# doorbellboard.net
KiCad netlist of a schematic drawn in EAGLE
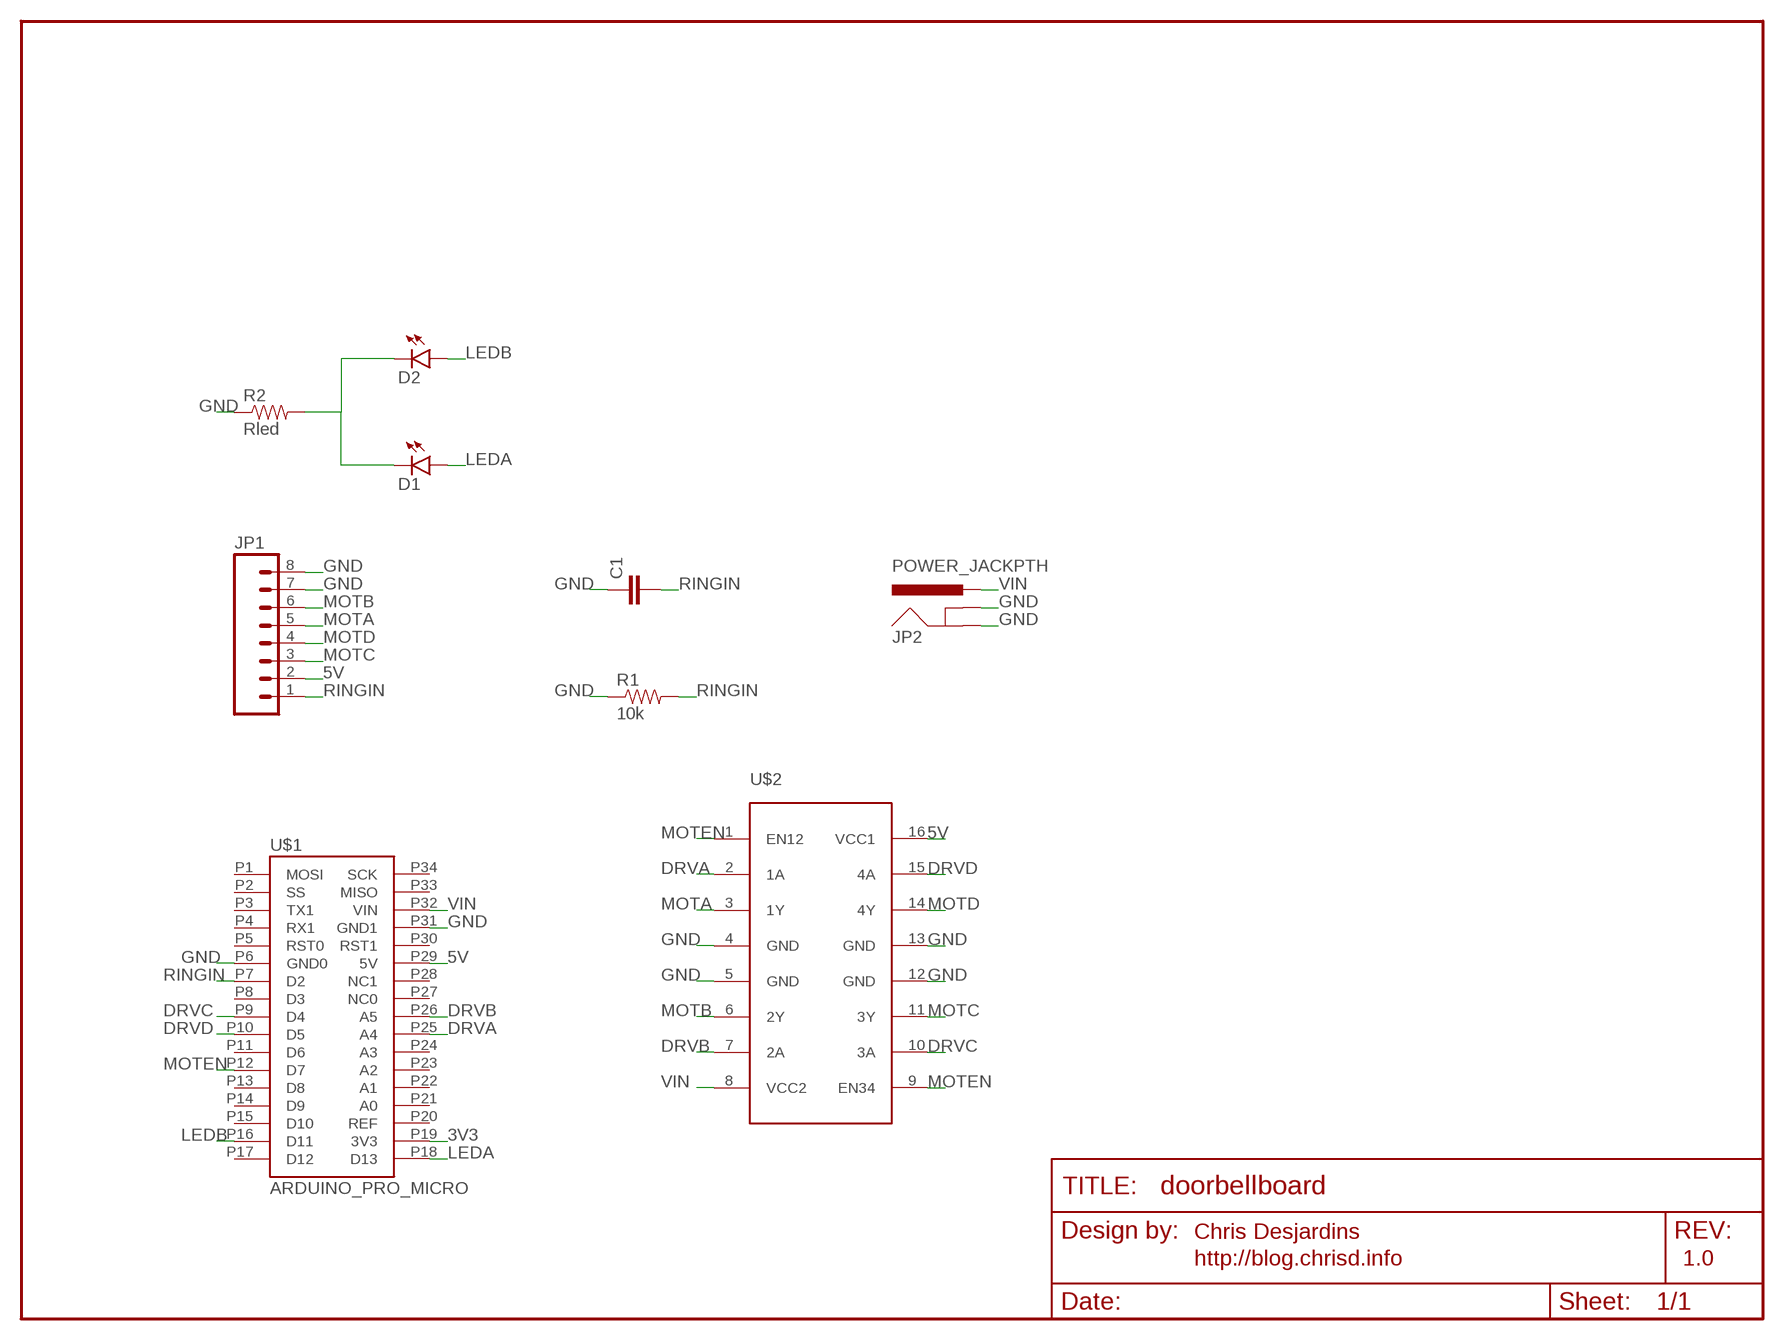
[diagram p0: schematic, sheet 1]

(export (version "E")
  (design (tool "Eeschema 10.0.6"))
  (components
    (comp (ref "C1")
      (value "0.1UF-50V-20%(PTH)KIT-EZ")
      (footprint "eagle-import:CAP-PTH-SMALL-KIT")
      (libsource (lib "eagle-import") (part "0.1UF-50V-20%(PTH)KIT-EZ"))
    )
    (comp (ref "D1")
      (value "LED-3MM-NO_SILK")
      (footprint "eagle-import:LED3MM-NS")
      (libsource (lib "eagle-import") (part "LED-3MM-NO_SILK"))
    )
    (comp (ref "D2")
      (value "LED-3MM-NO_SILK")
      (footprint "eagle-import:LED3MM-NS")
      (libsource (lib "eagle-import") (part "LED-3MM-NO_SILK"))
    )
    (comp (ref "JP1")
      (value "M08")
      (footprint "eagle-import:1X08_ROUND")
      (libsource (lib "eagle-import") (part "M08"))
    )
    (comp (ref "JP2")
      (value "POWER_JACKPTH")
      (footprint "eagle-import:POWER_JACK_PTH")
      (libsource (lib "eagle-import") (part "POWER_JACKPTH"))
    )
    (comp (ref "R1")
      (value "10k")
      (footprint "eagle-import:AXIAL-0.3")
      (libsource (lib "eagle-import") (part "10KOHM-1/4W-1%(PTH)HORIZ"))
    )
    (comp (ref "R2")
      (value "Rled")
      (footprint "eagle-import:AXIAL-0.3")
      (libsource (lib "eagle-import") (part "10KOHM-1/4W-1%(PTH)HORIZ"))
    )
    (comp (ref "U$1")
      (value "ARDUINO_PRO_MICRO")
      (footprint "eagle-import:ARDUINO_PRO_MICRO")
      (libsource (lib "eagle-import") (part "ARDUINO_PRO_MICRO"))
    )
    (comp (ref "U$2")
      (value "SN754410")
      (footprint "eagle-import:DIL16-KIT")
      (libsource (lib "eagle-import") (part "SN754410"))
    )
  )
  (nets
    (net (code "1") (name "/3V3") (class "Default")
      (node (ref "U$1") (pin "P19") (pinfunction "3V3_P19") (pintype "power_in"))
    )
    (net (code "2") (name "/5V") (class "Default")
      (node (ref "JP1") (pin "2") (pinfunction "2_2") (pintype "passive"))
      (node (ref "U$1") (pin "P29") (pinfunction "5V_P29") (pintype "power_in"))
      (node (ref "U$2") (pin "16") (pinfunction "VCC1_16") (pintype "bidirectional"))
    )
    (net (code "3") (name "/DRVA") (class "Default")
      (node (ref "U$1") (pin "P25") (pinfunction "A4_P25") (pintype "bidirectional"))
      (node (ref "U$2") (pin "2") (pinfunction "1A_2") (pintype "bidirectional"))
    )
    (net (code "4") (name "/DRVB") (class "Default")
      (node (ref "U$1") (pin "P26") (pinfunction "A5_P26") (pintype "bidirectional"))
      (node (ref "U$2") (pin "7") (pinfunction "2A_7") (pintype "bidirectional"))
    )
    (net (code "5") (name "/DRVC") (class "Default")
      (node (ref "U$1") (pin "P9") (pinfunction "D4_P9") (pintype "bidirectional"))
      (node (ref "U$2") (pin "10") (pinfunction "3A_10") (pintype "bidirectional"))
    )
    (net (code "6") (name "/DRVD") (class "Default")
      (node (ref "U$1") (pin "P10") (pinfunction "D5_P10") (pintype "bidirectional"))
      (node (ref "U$2") (pin "15") (pinfunction "4A_15") (pintype "bidirectional"))
    )
    (net (code "7") (name "/GND") (class "Default")
      (node (ref "C1") (pin "1") (pinfunction "1_1") (pintype "passive"))
      (node (ref "JP1") (pin "7") (pinfunction "7_7") (pintype "passive"))
      (node (ref "JP1") (pin "8") (pinfunction "8_8") (pintype "passive"))
      (node (ref "JP2") (pin "GND") (pinfunction "GND_GND") (pintype "bidirectional"))
      (node (ref "JP2") (pin "GNDBREAK") (pinfunction "GNDBREAK_GNDBREAK") (pintype "bidirectional"))
      (node (ref "R1") (pin "P$1") (pinfunction "1_P$1") (pintype "passive"))
      (node (ref "R2") (pin "P$1") (pinfunction "1_P$1") (pintype "passive"))
      (node (ref "U$1") (pin "P31") (pinfunction "GND1_P31") (pintype "power_in"))
      (node (ref "U$1") (pin "P6") (pinfunction "GND0_P6") (pintype "power_in"))
      (node (ref "U$2") (pin "12") (pinfunction "GND_12") (pintype "bidirectional"))
      (node (ref "U$2") (pin "13") (pinfunction "GND_13") (pintype "bidirectional"))
      (node (ref "U$2") (pin "4") (pinfunction "GND_4") (pintype "bidirectional"))
      (node (ref "U$2") (pin "5") (pinfunction "GND_5") (pintype "bidirectional"))
    )
    (net (code "8") (name "/LEDA") (class "Default")
      (node (ref "D1") (pin "A") (pinfunction "A_A") (pintype "passive"))
      (node (ref "U$1") (pin "P18") (pinfunction "D13_P18") (pintype "bidirectional"))
    )
    (net (code "9") (name "/LEDB") (class "Default")
      (node (ref "D2") (pin "A") (pinfunction "A_A") (pintype "passive"))
      (node (ref "U$1") (pin "P16") (pinfunction "D11_P16") (pintype "bidirectional"))
    )
    (net (code "10") (name "/MOTA") (class "Default")
      (node (ref "JP1") (pin "5") (pinfunction "5_5") (pintype "passive"))
      (node (ref "U$2") (pin "3") (pinfunction "1Y_3") (pintype "bidirectional"))
    )
    (net (code "11") (name "/MOTB") (class "Default")
      (node (ref "JP1") (pin "6") (pinfunction "6_6") (pintype "passive"))
      (node (ref "U$2") (pin "6") (pinfunction "2Y_6") (pintype "bidirectional"))
    )
    (net (code "12") (name "/MOTC") (class "Default")
      (node (ref "JP1") (pin "3") (pinfunction "3_3") (pintype "passive"))
      (node (ref "U$2") (pin "11") (pinfunction "3Y_11") (pintype "bidirectional"))
    )
    (net (code "13") (name "/MOTD") (class "Default")
      (node (ref "JP1") (pin "4") (pinfunction "4_4") (pintype "passive"))
      (node (ref "U$2") (pin "14") (pinfunction "4Y_14") (pintype "bidirectional"))
    )
    (net (code "14") (name "/MOTEN") (class "Default")
      (node (ref "U$1") (pin "P12") (pinfunction "D7_P12") (pintype "bidirectional"))
      (node (ref "U$2") (pin "1") (pinfunction "EN12_1") (pintype "bidirectional"))
      (node (ref "U$2") (pin "9") (pinfunction "EN34_9") (pintype "bidirectional"))
    )
    (net (code "15") (name "/REF") (class "Default")
      (node (ref "U$1") (pin "P20") (pinfunction "REF_P20") (pintype "power_in"))
    )
    (net (code "16") (name "/RINGIN") (class "Default")
      (node (ref "C1") (pin "2") (pinfunction "2_2") (pintype "passive"))
      (node (ref "JP1") (pin "1") (pinfunction "1_1") (pintype "passive"))
      (node (ref "R1") (pin "P$2") (pinfunction "2_P$2") (pintype "passive"))
      (node (ref "U$1") (pin "P7") (pinfunction "D2_P7") (pintype "bidirectional"))
    )
    (net (code "17") (name "/VIN") (class "Default")
      (node (ref "JP2") (pin "PWR") (pinfunction "PWR_PWR") (pintype "bidirectional"))
      (node (ref "U$1") (pin "P32") (pinfunction "VIN_P32") (pintype "power_in"))
      (node (ref "U$2") (pin "8") (pinfunction "VCC2_8") (pintype "bidirectional"))
    )
    (net (code "18") (name "Net-(D1-C)") (class "Default")
      (node (ref "D1") (pin "K") (pinfunction "C_K") (pintype "passive"))
      (node (ref "D2") (pin "K") (pinfunction "C_K") (pintype "passive"))
      (node (ref "R2") (pin "P$2") (pinfunction "2_P$2") (pintype "passive"))
    )
    (net (code "19") (name "unconnected-(U$1-A0-PadP21)") (class "Default")
      (node (ref "U$1") (pin "P21") (pinfunction "A0_P21") (pintype "bidirectional"))
    )
    (net (code "20") (name "unconnected-(U$1-A1-PadP22)") (class "Default")
      (node (ref "U$1") (pin "P22") (pinfunction "A1_P22") (pintype "bidirectional"))
    )
    (net (code "21") (name "unconnected-(U$1-A2-PadP23)") (class "Default")
      (node (ref "U$1") (pin "P23") (pinfunction "A2_P23") (pintype "bidirectional"))
    )
    (net (code "22") (name "unconnected-(U$1-A3-PadP24)") (class "Default")
      (node (ref "U$1") (pin "P24") (pinfunction "A3_P24") (pintype "bidirectional"))
    )
    (net (code "23") (name "unconnected-(U$1-D3-PadP8)") (class "Default")
      (node (ref "U$1") (pin "P8") (pinfunction "D3_P8") (pintype "bidirectional"))
    )
    (net (code "24") (name "unconnected-(U$1-D6-PadP11)") (class "Default")
      (node (ref "U$1") (pin "P11") (pinfunction "D6_P11") (pintype "bidirectional"))
    )
    (net (code "25") (name "unconnected-(U$1-D8-PadP13)") (class "Default")
      (node (ref "U$1") (pin "P13") (pinfunction "D8_P13") (pintype "bidirectional"))
    )
    (net (code "26") (name "unconnected-(U$1-D9-PadP14)") (class "Default")
      (node (ref "U$1") (pin "P14") (pinfunction "D9_P14") (pintype "bidirectional"))
    )
    (net (code "27") (name "unconnected-(U$1-D10-PadP15)") (class "Default")
      (node (ref "U$1") (pin "P15") (pinfunction "D10_P15") (pintype "bidirectional"))
    )
    (net (code "28") (name "unconnected-(U$1-D12-PadP17)") (class "Default")
      (node (ref "U$1") (pin "P17") (pinfunction "D12_P17") (pintype "bidirectional"))
    )
    (net (code "29") (name "unconnected-(U$1-MISO-PadP33)") (class "Default")
      (node (ref "U$1") (pin "P33") (pinfunction "MISO_P33") (pintype "bidirectional"))
    )
    (net (code "30") (name "unconnected-(U$1-MOSI-PadP1)") (class "Default")
      (node (ref "U$1") (pin "P1") (pinfunction "MOSI_P1") (pintype "bidirectional"))
    )
    (net (code "31") (name "unconnected-(U$1-NC0-PadP27)") (class "Default")
      (node (ref "U$1") (pin "P27") (pinfunction "NC0_P27") (pintype "no_connect"))
    )
    (net (code "32") (name "unconnected-(U$1-NC1-PadP28)") (class "Default")
      (node (ref "U$1") (pin "P28") (pinfunction "NC1_P28") (pintype "no_connect"))
    )
    (net (code "33") (name "unconnected-(U$1-RST0-PadP5)") (class "Default")
      (node (ref "U$1") (pin "P5") (pinfunction "RST0_P5") (pintype "bidirectional"))
    )
    (net (code "34") (name "unconnected-(U$1-RST1-PadP30)") (class "Default")
      (node (ref "U$1") (pin "P30") (pinfunction "RST1_P30") (pintype "bidirectional"))
    )
    (net (code "35") (name "unconnected-(U$1-RX1-PadP4)") (class "Default")
      (node (ref "U$1") (pin "P4") (pinfunction "RX1_P4") (pintype "bidirectional"))
    )
    (net (code "36") (name "unconnected-(U$1-SCK-PadP34)") (class "Default")
      (node (ref "U$1") (pin "P34") (pinfunction "SCK_P34") (pintype "bidirectional"))
    )
    (net (code "37") (name "unconnected-(U$1-SS-PadP2)") (class "Default")
      (node (ref "U$1") (pin "P2") (pinfunction "SS_P2") (pintype "bidirectional"))
    )
    (net (code "38") (name "unconnected-(U$1-TX1-PadP3)") (class "Default")
      (node (ref "U$1") (pin "P3") (pinfunction "TX1_P3") (pintype "bidirectional"))
    )
  )
)
